# ADC.net
KiCad netlist of a schematic drawn in EAGLE
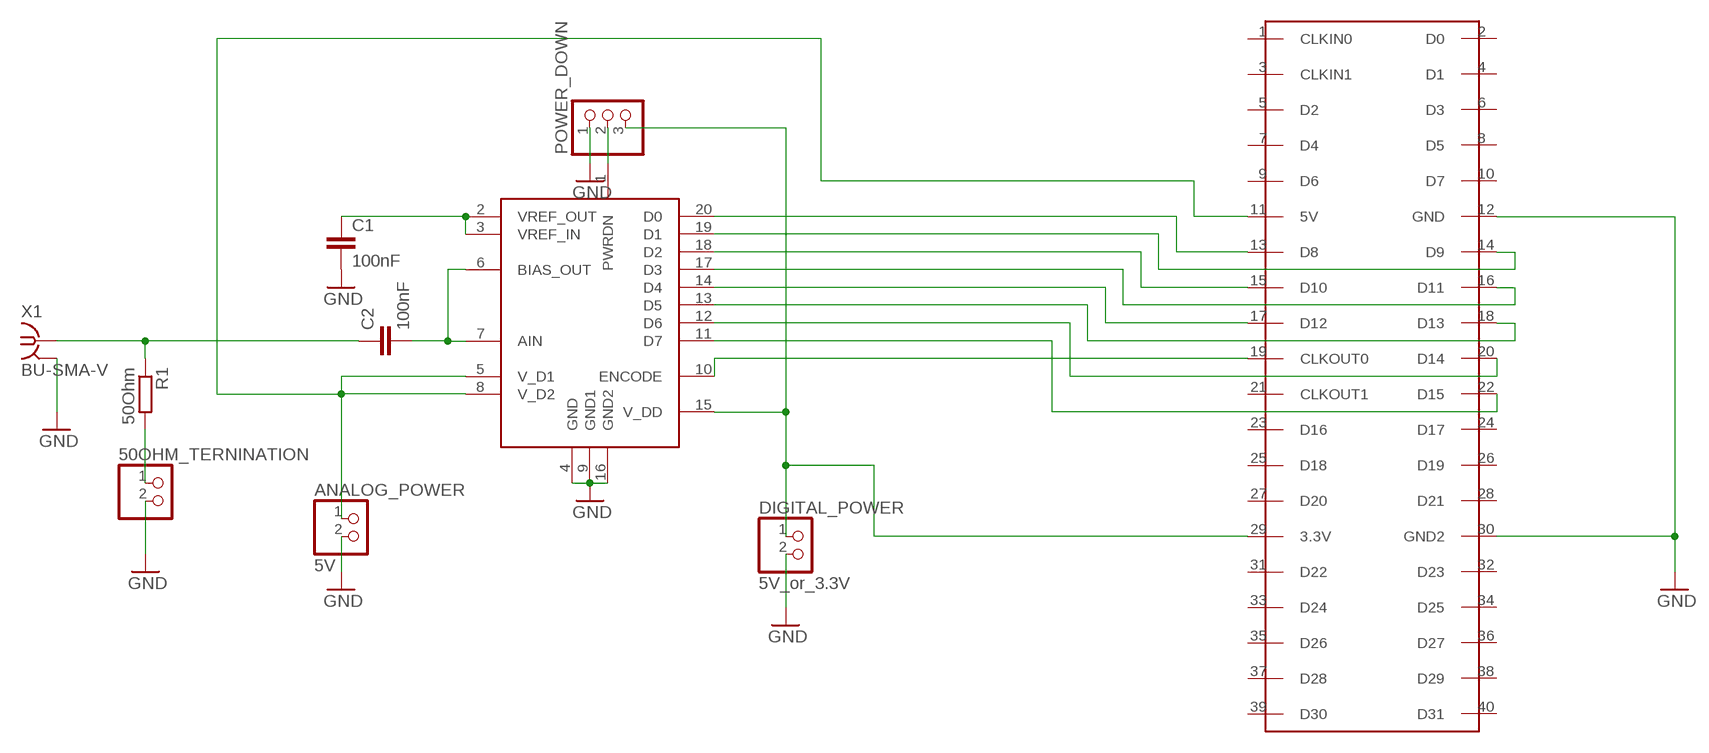
[diagram p0: schematic, sheet 1]

(export (version "E")
  (design (tool "Eeschema 10.0.6"))
  (components
    (comp (ref "50OHM_TERNINATION")
      (value "PINHD-1X2")
      (footprint "eagle-import:1X02")
      (libsource (lib "eagle-import") (part "PINHD-1X2"))
    )
    (comp (ref "ANALOG_POWER")
      (value "5V")
      (footprint "eagle-import:1X02")
      (libsource (lib "eagle-import") (part "PINHD-1X2"))
    )
    (comp (ref "C1")
      (value "100nF")
      (footprint "eagle-import:C2.5-5")
      (libsource (lib "eagle-import") (part "C2.5/5"))
    )
    (comp (ref "C2")
      (value "100nF")
      (footprint "eagle-import:C2.5-5")
      (libsource (lib "eagle-import") (part "C2.5/5"))
    )
    (comp (ref "DIGITAL_POWER")
      (value "5V_or_3.3V")
      (footprint "eagle-import:1X02")
      (libsource (lib "eagle-import") (part "PINHD-1X2"))
    )
    (comp (ref "POWER_DOWN")
      (value "PINHD-1X3")
      (footprint "eagle-import:1X03")
      (libsource (lib "eagle-import") (part "PINHD-1X3"))
    )
    (comp (ref "R1")
      (value "50Ohm")
      (footprint "eagle-import:0207_10")
      (libsource (lib "eagle-import") (part "R-EU_0207/10"))
    )
    (comp (ref "U$1")
      (value "AD9057")
      (footprint "eagle-import:SSOP20")
      (libsource (lib "eagle-import") (part "AD9057"))
    )
    (comp (ref "U$2")
      (value "FPGA_GPIO_DE0")
      (footprint "eagle-import:2X20")
      (libsource (lib "eagle-import") (part "FPGA_GPIO_DE0"))
    )
    (comp (ref "X1")
      (value "BU-SMA-V")
      (footprint "eagle-import:BU-SMA-V")
      (libsource (lib "eagle-import") (part "BU-SMA-V"))
    )
  )
  (nets
    (net (code "1") (name "GND") (class "Default")
      (node (ref "50OHM_TERNINATION") (pin "2") (pinfunction "2_2") (pintype "passive"))
      (node (ref "ANALOG_POWER") (pin "2") (pinfunction "2_2") (pintype "passive"))
      (node (ref "C1") (pin "2") (pinfunction "2_2") (pintype "passive"))
      (node (ref "DIGITAL_POWER") (pin "2") (pinfunction "2_2") (pintype "passive"))
      (node (ref "POWER_DOWN") (pin "1") (pinfunction "1_1") (pintype "passive"))
      (node (ref "U$1") (pin "16") (pinfunction "GND2_16") (pintype "bidirectional"))
      (node (ref "U$1") (pin "4") (pinfunction "GND_4") (pintype "bidirectional"))
      (node (ref "U$1") (pin "9") (pinfunction "GND1_9") (pintype "bidirectional"))
      (node (ref "U$2") (pin "12") (pinfunction "GND_12") (pintype "bidirectional"))
      (node (ref "U$2") (pin "30") (pinfunction "GND2_30") (pintype "bidirectional"))
      (node (ref "X1") (pin "2") (pinfunction "2_2") (pintype "passive"))
      (node (ref "X1") (pin "3") (pinfunction "2_3") (pintype "passive"))
      (node (ref "X1") (pin "4") (pinfunction "2_4") (pintype "passive"))
      (node (ref "X1") (pin "5") (pinfunction "2_5") (pintype "passive"))
    )
    (net (code "2") (name "Net-(50OHM_TERNINATION-Pad1)") (class "Default")
      (node (ref "50OHM_TERNINATION") (pin "1") (pinfunction "1_1") (pintype "passive"))
      (node (ref "R1") (pin "2") (pinfunction "2_2") (pintype "passive"))
    )
    (net (code "3") (name "Net-(C2-Pad1)") (class "Default")
      (node (ref "C2") (pin "1") (pinfunction "1_1") (pintype "passive"))
      (node (ref "R1") (pin "1") (pinfunction "1_1") (pintype "passive"))
      (node (ref "X1") (pin "1") (pinfunction "1_1") (pintype "passive"))
    )
    (net (code "4") (name "Net-(U$1-AIN)") (class "Default")
      (node (ref "C2") (pin "2") (pinfunction "2_2") (pintype "passive"))
      (node (ref "U$1") (pin "6") (pinfunction "BIAS_OUT_6") (pintype "bidirectional"))
      (node (ref "U$1") (pin "7") (pinfunction "AIN_7") (pintype "bidirectional"))
    )
    (net (code "5") (name "Net-(U$1-D0)") (class "Default")
      (node (ref "U$1") (pin "20") (pinfunction "D0_20") (pintype "bidirectional"))
      (node (ref "U$2") (pin "13") (pinfunction "D8_13") (pintype "bidirectional"))
    )
    (net (code "6") (name "Net-(U$1-D1)") (class "Default")
      (node (ref "U$1") (pin "19") (pinfunction "D1_19") (pintype "bidirectional"))
      (node (ref "U$2") (pin "14") (pinfunction "D9_14") (pintype "bidirectional"))
    )
    (net (code "7") (name "Net-(U$1-D2)") (class "Default")
      (node (ref "U$1") (pin "18") (pinfunction "D2_18") (pintype "bidirectional"))
      (node (ref "U$2") (pin "15") (pinfunction "D10_15") (pintype "bidirectional"))
    )
    (net (code "8") (name "Net-(U$1-D3)") (class "Default")
      (node (ref "U$1") (pin "17") (pinfunction "D3_17") (pintype "bidirectional"))
      (node (ref "U$2") (pin "16") (pinfunction "D11_16") (pintype "bidirectional"))
    )
    (net (code "9") (name "Net-(U$1-D4)") (class "Default")
      (node (ref "U$1") (pin "14") (pinfunction "D4_14") (pintype "bidirectional"))
      (node (ref "U$2") (pin "17") (pinfunction "D12_17") (pintype "bidirectional"))
    )
    (net (code "10") (name "Net-(U$1-D5)") (class "Default")
      (node (ref "U$1") (pin "13") (pinfunction "D5_13") (pintype "bidirectional"))
      (node (ref "U$2") (pin "18") (pinfunction "D13_18") (pintype "bidirectional"))
    )
    (net (code "11") (name "Net-(U$1-D6)") (class "Default")
      (node (ref "U$1") (pin "12") (pinfunction "D6_12") (pintype "bidirectional"))
      (node (ref "U$2") (pin "20") (pinfunction "D14_20") (pintype "bidirectional"))
    )
    (net (code "12") (name "Net-(U$1-D7)") (class "Default")
      (node (ref "U$1") (pin "11") (pinfunction "D7_11") (pintype "bidirectional"))
      (node (ref "U$2") (pin "22") (pinfunction "D15_22") (pintype "bidirectional"))
    )
    (net (code "13") (name "Net-(U$1-ENCODE)") (class "Default")
      (node (ref "U$1") (pin "10") (pinfunction "ENCODE_10") (pintype "bidirectional"))
      (node (ref "U$2") (pin "19") (pinfunction "CLKOUT0_19") (pintype "bidirectional"))
    )
    (net (code "14") (name "Net-(U$1-PWRDN)") (class "Default")
      (node (ref "POWER_DOWN") (pin "2") (pinfunction "2_2") (pintype "passive"))
      (node (ref "U$1") (pin "1") (pinfunction "PWRDN_1") (pintype "bidirectional"))
    )
    (net (code "15") (name "Net-(U$1-VREF_IN)") (class "Default")
      (node (ref "C1") (pin "1") (pinfunction "1_1") (pintype "passive"))
      (node (ref "U$1") (pin "2") (pinfunction "VREF_OUT_2") (pintype "bidirectional"))
      (node (ref "U$1") (pin "3") (pinfunction "VREF_IN_3") (pintype "bidirectional"))
    )
    (net (code "16") (name "Net-(U$1-V_D1)") (class "Default")
      (node (ref "ANALOG_POWER") (pin "1") (pinfunction "1_1") (pintype "passive"))
      (node (ref "U$1") (pin "5") (pinfunction "V_D1_5") (pintype "bidirectional"))
      (node (ref "U$1") (pin "8") (pinfunction "V_D2_8") (pintype "bidirectional"))
      (node (ref "U$2") (pin "11") (pinfunction "5V_11") (pintype "bidirectional"))
    )
    (net (code "17") (name "Net-(U$1-V_DD)") (class "Default")
      (node (ref "DIGITAL_POWER") (pin "1") (pinfunction "1_1") (pintype "passive"))
      (node (ref "POWER_DOWN") (pin "3") (pinfunction "3_3") (pintype "passive"))
      (node (ref "U$1") (pin "15") (pinfunction "V_DD_15") (pintype "bidirectional"))
      (node (ref "U$2") (pin "29") (pinfunction "3.3V_29") (pintype "bidirectional"))
    )
    (net (code "18") (name "unconnected-(U$2-CLKIN0-Pad1)") (class "Default")
      (node (ref "U$2") (pin "1") (pinfunction "CLKIN0_1") (pintype "bidirectional"))
    )
    (net (code "19") (name "unconnected-(U$2-CLKIN1-Pad3)") (class "Default")
      (node (ref "U$2") (pin "3") (pinfunction "CLKIN1_3") (pintype "bidirectional"))
    )
    (net (code "20") (name "unconnected-(U$2-CLKOUT1-Pad21)") (class "Default")
      (node (ref "U$2") (pin "21") (pinfunction "CLKOUT1_21") (pintype "bidirectional"))
    )
    (net (code "21") (name "unconnected-(U$2-D0-Pad2)") (class "Default")
      (node (ref "U$2") (pin "2") (pinfunction "D0_2") (pintype "bidirectional"))
    )
    (net (code "22") (name "unconnected-(U$2-D1-Pad4)") (class "Default")
      (node (ref "U$2") (pin "4") (pinfunction "D1_4") (pintype "bidirectional"))
    )
    (net (code "23") (name "unconnected-(U$2-D2-Pad5)") (class "Default")
      (node (ref "U$2") (pin "5") (pinfunction "D2_5") (pintype "bidirectional"))
    )
    (net (code "24") (name "unconnected-(U$2-D3-Pad6)") (class "Default")
      (node (ref "U$2") (pin "6") (pinfunction "D3_6") (pintype "bidirectional"))
    )
    (net (code "25") (name "unconnected-(U$2-D4-Pad7)") (class "Default")
      (node (ref "U$2") (pin "7") (pinfunction "D4_7") (pintype "bidirectional"))
    )
    (net (code "26") (name "unconnected-(U$2-D5-Pad8)") (class "Default")
      (node (ref "U$2") (pin "8") (pinfunction "D5_8") (pintype "bidirectional"))
    )
    (net (code "27") (name "unconnected-(U$2-D6-Pad9)") (class "Default")
      (node (ref "U$2") (pin "9") (pinfunction "D6_9") (pintype "bidirectional"))
    )
    (net (code "28") (name "unconnected-(U$2-D7-Pad10)") (class "Default")
      (node (ref "U$2") (pin "10") (pinfunction "D7_10") (pintype "bidirectional"))
    )
    (net (code "29") (name "unconnected-(U$2-D16-Pad23)") (class "Default")
      (node (ref "U$2") (pin "23") (pinfunction "D16_23") (pintype "bidirectional"))
    )
    (net (code "30") (name "unconnected-(U$2-D17-Pad24)") (class "Default")
      (node (ref "U$2") (pin "24") (pinfunction "D17_24") (pintype "bidirectional"))
    )
    (net (code "31") (name "unconnected-(U$2-D18-Pad25)") (class "Default")
      (node (ref "U$2") (pin "25") (pinfunction "D18_25") (pintype "bidirectional"))
    )
    (net (code "32") (name "unconnected-(U$2-D19-Pad26)") (class "Default")
      (node (ref "U$2") (pin "26") (pinfunction "D19_26") (pintype "bidirectional"))
    )
    (net (code "33") (name "unconnected-(U$2-D20-Pad27)") (class "Default")
      (node (ref "U$2") (pin "27") (pinfunction "D20_27") (pintype "bidirectional"))
    )
    (net (code "34") (name "unconnected-(U$2-D21-Pad28)") (class "Default")
      (node (ref "U$2") (pin "28") (pinfunction "D21_28") (pintype "bidirectional"))
    )
    (net (code "35") (name "unconnected-(U$2-D22-Pad31)") (class "Default")
      (node (ref "U$2") (pin "31") (pinfunction "D22_31") (pintype "bidirectional"))
    )
    (net (code "36") (name "unconnected-(U$2-D23-Pad32)") (class "Default")
      (node (ref "U$2") (pin "32") (pinfunction "D23_32") (pintype "bidirectional"))
    )
    (net (code "37") (name "unconnected-(U$2-D24-Pad33)") (class "Default")
      (node (ref "U$2") (pin "33") (pinfunction "D24_33") (pintype "bidirectional"))
    )
    (net (code "38") (name "unconnected-(U$2-D25-Pad34)") (class "Default")
      (node (ref "U$2") (pin "34") (pinfunction "D25_34") (pintype "bidirectional"))
    )
    (net (code "39") (name "unconnected-(U$2-D26-Pad35)") (class "Default")
      (node (ref "U$2") (pin "35") (pinfunction "D26_35") (pintype "bidirectional"))
    )
    (net (code "40") (name "unconnected-(U$2-D27-Pad36)") (class "Default")
      (node (ref "U$2") (pin "36") (pinfunction "D27_36") (pintype "bidirectional"))
    )
    (net (code "41") (name "unconnected-(U$2-D28-Pad37)") (class "Default")
      (node (ref "U$2") (pin "37") (pinfunction "D28_37") (pintype "bidirectional"))
    )
    (net (code "42") (name "unconnected-(U$2-D29-Pad38)") (class "Default")
      (node (ref "U$2") (pin "38") (pinfunction "D29_38") (pintype "bidirectional"))
    )
    (net (code "43") (name "unconnected-(U$2-D30-Pad39)") (class "Default")
      (node (ref "U$2") (pin "39") (pinfunction "D30_39") (pintype "bidirectional"))
    )
    (net (code "44") (name "unconnected-(U$2-D31-Pad40)") (class "Default")
      (node (ref "U$2") (pin "40") (pinfunction "D31_40") (pintype "bidirectional"))
    )
  )
)
